# senpai.net
KiCad netlist of a schematic drawn in EAGLE
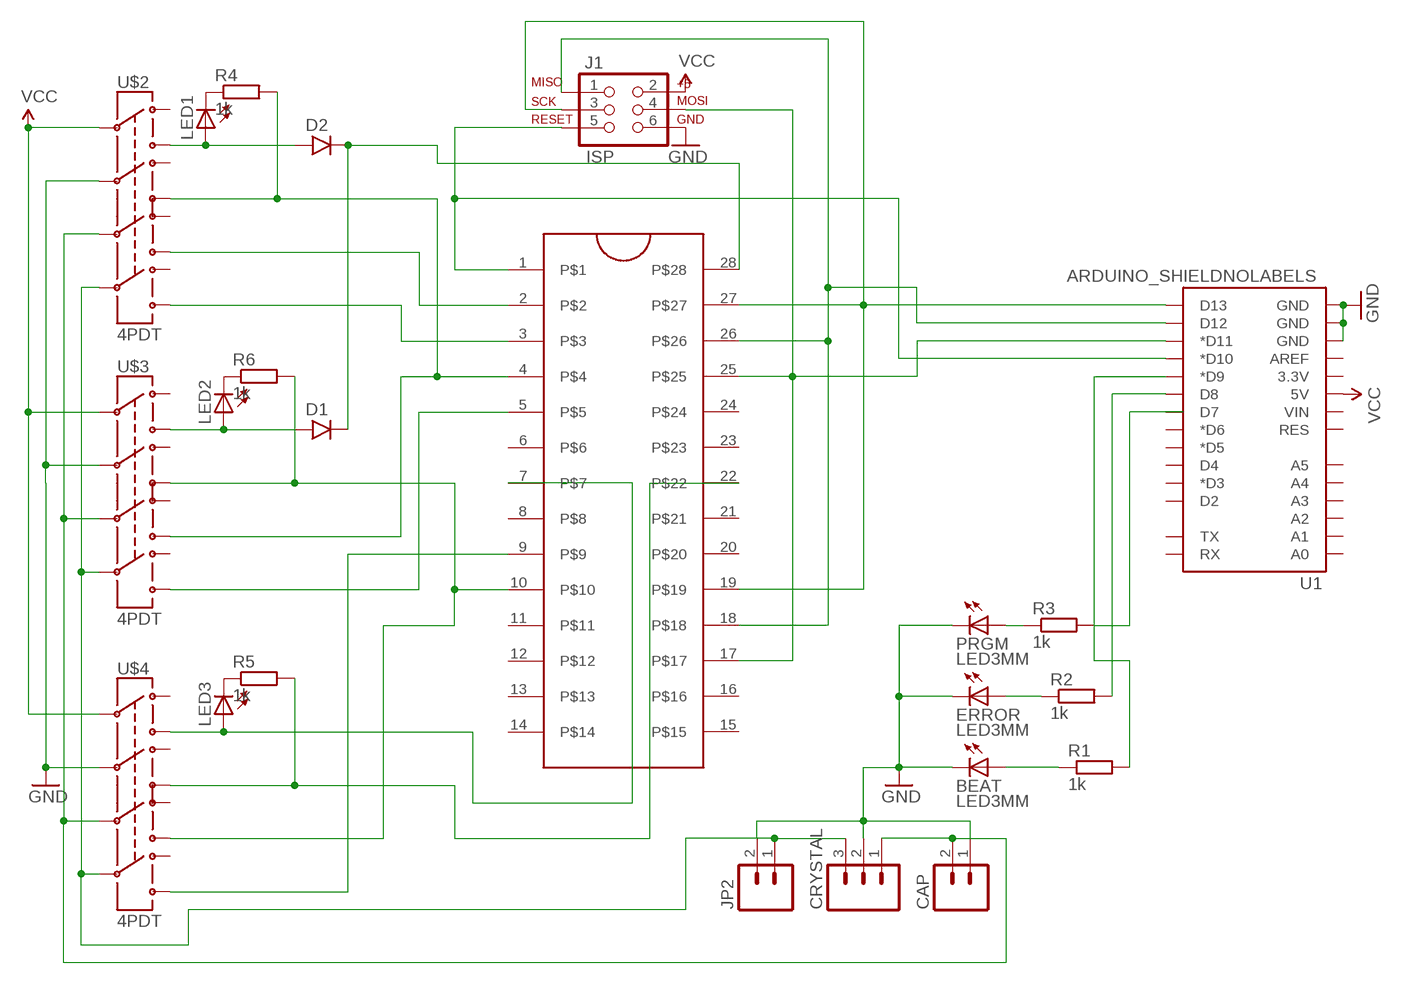
[diagram p0: schematic, sheet 1]

(export (version "E")
  (design (tool "Eeschema 10.0.6"))
  (components
    (comp (ref "BEAT")
      (value "LED3MM")
      (footprint "eagle-import:LED5MM")
      (libsource (lib "eagle-import") (part "LED5MM"))
    )
    (comp (ref "CAP")
      (value "M02PTH")
      (footprint "eagle-import:1X02")
      (libsource (lib "eagle-import") (part "M02PTH"))
    )
    (comp (ref "CRYSTAL")
      (value "M03LOCK")
      (footprint "eagle-import:1X03_LOCK")
      (libsource (lib "eagle-import") (part "M03LOCK"))
    )
    (comp (ref "D1")
      (value "DO41.2")
      (footprint "eagle-import:DO41-2")
      (libsource (lib "eagle-import") (part "DO41.2"))
    )
    (comp (ref "D2")
      (value "DO41.2")
      (footprint "eagle-import:DO41-2")
      (libsource (lib "eagle-import") (part "DO41.2"))
    )
    (comp (ref "ERROR")
      (value "LED3MM")
      (footprint "eagle-import:LED5MM")
      (libsource (lib "eagle-import") (part "LED5MM"))
    )
    (comp (ref "J1")
      (value "ISP")
      (footprint "eagle-import:2X3")
      (libsource (lib "eagle-import") (part "AVR_SPI_PRG_6PTH"))
    )
    (comp (ref "JP2")
      (value "M02PTH")
      (footprint "eagle-import:1X02")
      (libsource (lib "eagle-import") (part "M02PTH"))
    )
    (comp (ref "LED1")
      (value "LED5MM")
      (footprint "eagle-import:LED5MM")
      (libsource (lib "eagle-import") (part "LED5MM"))
    )
    (comp (ref "LED2")
      (value "LED5MM")
      (footprint "eagle-import:LED5MM")
      (libsource (lib "eagle-import") (part "LED5MM"))
    )
    (comp (ref "LED3")
      (value "LED5MM")
      (footprint "eagle-import:LED5MM")
      (libsource (lib "eagle-import") (part "LED5MM"))
    )
    (comp (ref "PRGM")
      (value "LED3MM")
      (footprint "eagle-import:LED5MM")
      (libsource (lib "eagle-import") (part "LED5MM"))
    )
    (comp (ref "R1")
      (value "1k")
      (footprint "eagle-import:0204_7")
      (libsource (lib "eagle-import") (part "R-EU_0204/7"))
    )
    (comp (ref "R2")
      (value "1k")
      (footprint "eagle-import:0204_7")
      (libsource (lib "eagle-import") (part "R-EU_0204/7"))
    )
    (comp (ref "R3")
      (value "1k")
      (footprint "eagle-import:0204_7")
      (libsource (lib "eagle-import") (part "R-EU_0204/7"))
    )
    (comp (ref "R4")
      (value "1k")
      (footprint "eagle-import:0204_7")
      (libsource (lib "eagle-import") (part "R-EU_0204/7"))
    )
    (comp (ref "R5")
      (value "1k")
      (footprint "eagle-import:0204_7")
      (libsource (lib "eagle-import") (part "R-EU_0204/7"))
    )
    (comp (ref "R6")
      (value "1k")
      (footprint "eagle-import:0204_7")
      (libsource (lib "eagle-import") (part "R-EU_0204/7"))
    )
    (comp (ref "U$1")
      (value "ZIFSOCKET-28-3ZIFFSOCKET-28-3")
      (footprint "eagle-import:DIL28-3-ZIF_SOCKET")
      (libsource (lib "eagle-import") (part "ZIFSOCKET-28-3ZIFFSOCKET-28-3"))
    )
    (comp (ref "U$2")
      (value "4PDT")
      (footprint "eagle-import:4PDT")
      (libsource (lib "eagle-import") (part "4PDT"))
    )
    (comp (ref "U$3")
      (value "4PDT")
      (footprint "eagle-import:4PDT")
      (libsource (lib "eagle-import") (part "4PDT"))
    )
    (comp (ref "U$4")
      (value "4PDT")
      (footprint "eagle-import:4PDT")
      (libsource (lib "eagle-import") (part "4PDT"))
    )
    (comp (ref "U1")
      (value "ARDUINO_SHIELDNOLABELS")
      (footprint "eagle-import:DUEMILANOVE_SHIELD_NOLABELS")
      (libsource (lib "eagle-import") (part "ARDUINO_SHIELDNOLABELS"))
    )
  )
  (nets
    (net (code "1") (name "GND") (class "Default")
      (node (ref "BEAT") (pin "K") (pinfunction "C_K") (pintype "passive"))
      (node (ref "CAP") (pin "1") (pinfunction "1_1") (pintype "passive"))
      (node (ref "CRYSTAL") (pin "2") (pinfunction "2_2") (pintype "passive"))
      (node (ref "ERROR") (pin "K") (pinfunction "C_K") (pintype "passive"))
      (node (ref "J1") (pin "6") (pinfunction "6_6") (pintype "passive"))
      (node (ref "JP2") (pin "2") (pinfunction "2_2") (pintype "passive"))
      (node (ref "PRGM") (pin "K") (pinfunction "C_K") (pintype "passive"))
      (node (ref "U$2") (pin "5") (pinfunction "5_5") (pintype "bidirectional"))
      (node (ref "U$3") (pin "5") (pinfunction "5_5") (pintype "bidirectional"))
      (node (ref "U$4") (pin "5") (pinfunction "5_5") (pintype "bidirectional"))
      (node (ref "U1") (pin "GND@0") (pinfunction "GND_GND@0") (pintype "bidirectional"))
      (node (ref "U1") (pin "GND@1") (pinfunction "GND_GND@1") (pintype "bidirectional"))
      (node (ref "U1") (pin "GND@2") (pinfunction "GND_GND@2") (pintype "bidirectional"))
    )
    (net (code "2") (name "Net-(BEAT-PadA)") (class "Default")
      (node (ref "BEAT") (pin "A") (pinfunction "A_A") (pintype "passive"))
      (node (ref "R1") (pin "1") (pinfunction "1_1") (pintype "passive"))
    )
    (net (code "3") (name "Net-(CAP-Pad2)") (class "Default")
      (node (ref "CAP") (pin "2") (pinfunction "2_2") (pintype "passive"))
      (node (ref "CRYSTAL") (pin "1") (pinfunction "1_1") (pintype "passive"))
      (node (ref "U$2") (pin "8") (pinfunction "8_8") (pintype "bidirectional"))
      (node (ref "U$3") (pin "8") (pinfunction "8_8") (pintype "bidirectional"))
      (node (ref "U$4") (pin "8") (pinfunction "8_8") (pintype "bidirectional"))
    )
    (net (code "4") (name "Net-(CRYSTAL-Pad3)") (class "Default")
      (node (ref "CRYSTAL") (pin "3") (pinfunction "3_3") (pintype "passive"))
      (node (ref "JP2") (pin "1") (pinfunction "1_1") (pintype "passive"))
      (node (ref "U$2") (pin "11") (pinfunction "11_11") (pintype "bidirectional"))
      (node (ref "U$3") (pin "11") (pinfunction "11_11") (pintype "bidirectional"))
      (node (ref "U$4") (pin "11") (pinfunction "11_11") (pintype "bidirectional"))
    )
    (net (code "5") (name "Net-(D1-PadA)") (class "Default")
      (node (ref "D1") (pin "A") (pinfunction "A_A") (pintype "passive"))
      (node (ref "LED2") (pin "A") (pinfunction "A_A") (pintype "passive"))
      (node (ref "U$3") (pin "3") (pinfunction "3_3") (pintype "bidirectional"))
    )
    (net (code "6") (name "Net-(D2-PadA)") (class "Default")
      (node (ref "D2") (pin "A") (pinfunction "A_A") (pintype "passive"))
      (node (ref "LED1") (pin "A") (pinfunction "A_A") (pintype "passive"))
      (node (ref "U$2") (pin "3") (pinfunction "3_3") (pintype "bidirectional"))
    )
    (net (code "7") (name "Net-(ERROR-PadA)") (class "Default")
      (node (ref "ERROR") (pin "A") (pinfunction "A_A") (pintype "passive"))
      (node (ref "R2") (pin "1") (pinfunction "1_1") (pintype "passive"))
    )
    (net (code "8") (name "Net-(LED1-C)") (class "Default")
      (node (ref "LED1") (pin "K") (pinfunction "C_K") (pintype "passive"))
      (node (ref "R4") (pin "1") (pinfunction "1_1") (pintype "passive"))
    )
    (net (code "9") (name "Net-(LED2-C)") (class "Default")
      (node (ref "LED2") (pin "K") (pinfunction "C_K") (pintype "passive"))
      (node (ref "R6") (pin "1") (pinfunction "1_1") (pintype "passive"))
    )
    (net (code "10") (name "Net-(LED3-C)") (class "Default")
      (node (ref "LED3") (pin "K") (pinfunction "C_K") (pintype "passive"))
      (node (ref "R5") (pin "1") (pinfunction "1_1") (pintype "passive"))
    )
    (net (code "11") (name "Net-(PRGM-PadA)") (class "Default")
      (node (ref "PRGM") (pin "A") (pinfunction "A_A") (pintype "passive"))
      (node (ref "R3") (pin "1") (pinfunction "1_1") (pintype "passive"))
    )
    (net (code "12") (name "Net-(R2-Pad2)") (class "Default")
      (node (ref "R2") (pin "2") (pinfunction "2_2") (pintype "passive"))
      (node (ref "U1") (pin "D8") (pinfunction "D8_D8") (pintype "bidirectional"))
    )
    (net (code "13") (name "Net-(R3-Pad2)") (class "Default")
      (node (ref "R3") (pin "2") (pinfunction "2_2") (pintype "passive"))
      (node (ref "U1") (pin "D7") (pinfunction "D7_D7") (pintype "bidirectional"))
    )
    (net (code "14") (name "Net-(U$1-P$1)") (class "Default")
      (node (ref "J1") (pin "5") (pinfunction "5_5") (pintype "passive"))
      (node (ref "U$1") (pin "1") (pinfunction "P$1_1") (pintype "bidirectional"))
      (node (ref "U1") (pin "D10") (pinfunction "*D10_D10") (pintype "bidirectional"))
    )
    (net (code "15") (name "Net-(U$1-P$2)") (class "Default")
      (node (ref "U$1") (pin "2") (pinfunction "P$2_2") (pintype "bidirectional"))
      (node (ref "U$2") (pin "9") (pinfunction "9_9") (pintype "bidirectional"))
    )
    (net (code "16") (name "Net-(U$1-P$3)") (class "Default")
      (node (ref "U$1") (pin "3") (pinfunction "P$3_3") (pintype "bidirectional"))
      (node (ref "U$2") (pin "12") (pinfunction "12_12") (pintype "bidirectional"))
    )
    (net (code "17") (name "Net-(U$1-P$4)") (class "Default")
      (node (ref "R4") (pin "2") (pinfunction "2_2") (pintype "passive"))
      (node (ref "U$1") (pin "4") (pinfunction "P$4_4") (pintype "bidirectional"))
      (node (ref "U$2") (pin "6") (pinfunction "6_6") (pintype "bidirectional"))
      (node (ref "U$3") (pin "9") (pinfunction "9_9") (pintype "bidirectional"))
    )
    (net (code "18") (name "Net-(U$1-P$5)") (class "Default")
      (node (ref "U$1") (pin "5") (pinfunction "P$5_5") (pintype "bidirectional"))
      (node (ref "U$3") (pin "12") (pinfunction "12_12") (pintype "bidirectional"))
    )
    (net (code "19") (name "Net-(U$1-P$7)") (class "Default")
      (node (ref "LED3") (pin "A") (pinfunction "A_A") (pintype "passive"))
      (node (ref "U$1") (pin "7") (pinfunction "P$7_7") (pintype "bidirectional"))
      (node (ref "U$4") (pin "3") (pinfunction "3_3") (pintype "bidirectional"))
    )
    (net (code "20") (name "Net-(U$1-P$9)") (class "Default")
      (node (ref "U$1") (pin "9") (pinfunction "P$9_9") (pintype "bidirectional"))
      (node (ref "U$4") (pin "12") (pinfunction "12_12") (pintype "bidirectional"))
    )
    (net (code "21") (name "Net-(U$1-P$10)") (class "Default")
      (node (ref "R6") (pin "2") (pinfunction "2_2") (pintype "passive"))
      (node (ref "U$1") (pin "10") (pinfunction "P$10_10") (pintype "bidirectional"))
      (node (ref "U$3") (pin "6") (pinfunction "6_6") (pintype "bidirectional"))
      (node (ref "U$4") (pin "9") (pinfunction "9_9") (pintype "bidirectional"))
    )
    (net (code "22") (name "Net-(U$1-P$17)") (class "Default")
      (node (ref "J1") (pin "4") (pinfunction "4_4") (pintype "passive"))
      (node (ref "U$1") (pin "17") (pinfunction "P$17_17") (pintype "bidirectional"))
      (node (ref "U$1") (pin "25") (pinfunction "P$25_25") (pintype "bidirectional"))
      (node (ref "U1") (pin "D11") (pinfunction "*D11_D11") (pintype "bidirectional"))
    )
    (net (code "23") (name "Net-(U$1-P$18)") (class "Default")
      (node (ref "J1") (pin "1") (pinfunction "1_1") (pintype "passive"))
      (node (ref "U$1") (pin "18") (pinfunction "P$18_18") (pintype "bidirectional"))
      (node (ref "U$1") (pin "26") (pinfunction "P$26_26") (pintype "bidirectional"))
      (node (ref "U1") (pin "D12") (pinfunction "D12_D12") (pintype "bidirectional"))
    )
    (net (code "24") (name "Net-(U$1-P$19)") (class "Default")
      (node (ref "J1") (pin "3") (pinfunction "3_3") (pintype "passive"))
      (node (ref "U$1") (pin "19") (pinfunction "P$19_19") (pintype "bidirectional"))
      (node (ref "U$1") (pin "27") (pinfunction "P$27_27") (pintype "bidirectional"))
      (node (ref "U1") (pin "D13") (pinfunction "D13_D13") (pintype "bidirectional"))
    )
    (net (code "25") (name "Net-(U$1-P$22)") (class "Default")
      (node (ref "R5") (pin "2") (pinfunction "2_2") (pintype "passive"))
      (node (ref "U$1") (pin "22") (pinfunction "P$22_22") (pintype "bidirectional"))
      (node (ref "U$4") (pin "6") (pinfunction "6_6") (pintype "bidirectional"))
    )
    (net (code "26") (name "Net-(U$1-P$28)") (class "Default")
      (node (ref "D1") (pin "C") (pinfunction "C_C") (pintype "passive"))
      (node (ref "D2") (pin "C") (pinfunction "C_C") (pintype "passive"))
      (node (ref "U$1") (pin "28") (pinfunction "P$28_28") (pintype "bidirectional"))
    )
    (net (code "27") (name "Net-(U1-*D9)") (class "Default")
      (node (ref "R1") (pin "2") (pinfunction "2_2") (pintype "passive"))
      (node (ref "U1") (pin "D9") (pinfunction "*D9_D9") (pintype "bidirectional"))
    )
    (net (code "28") (name "VCC") (class "Default")
      (node (ref "J1") (pin "2") (pinfunction "2_2") (pintype "passive"))
      (node (ref "U$2") (pin "2") (pinfunction "2_2") (pintype "bidirectional"))
      (node (ref "U$3") (pin "2") (pinfunction "2_2") (pintype "bidirectional"))
      (node (ref "U$4") (pin "2") (pinfunction "2_2") (pintype "bidirectional"))
      (node (ref "U1") (pin "5V") (pinfunction "5V_5V") (pintype "bidirectional"))
    )
    (net (code "29") (name "unconnected-(U$1-P$6-Pad6)") (class "Default")
      (node (ref "U$1") (pin "6") (pinfunction "P$6_6") (pintype "bidirectional"))
    )
    (net (code "30") (name "unconnected-(U$1-P$8-Pad8)") (class "Default")
      (node (ref "U$1") (pin "8") (pinfunction "P$8_8") (pintype "bidirectional"))
    )
    (net (code "31") (name "unconnected-(U$1-P$11-Pad11)") (class "Default")
      (node (ref "U$1") (pin "11") (pinfunction "P$11_11") (pintype "bidirectional"))
    )
    (net (code "32") (name "unconnected-(U$1-P$12-Pad12)") (class "Default")
      (node (ref "U$1") (pin "12") (pinfunction "P$12_12") (pintype "bidirectional"))
    )
    (net (code "33") (name "unconnected-(U$1-P$13-Pad13)") (class "Default")
      (node (ref "U$1") (pin "13") (pinfunction "P$13_13") (pintype "bidirectional"))
    )
    (net (code "34") (name "unconnected-(U$1-P$14-Pad14)") (class "Default")
      (node (ref "U$1") (pin "14") (pinfunction "P$14_14") (pintype "bidirectional"))
    )
    (net (code "35") (name "unconnected-(U$1-P$15-Pad15)") (class "Default")
      (node (ref "U$1") (pin "15") (pinfunction "P$15_15") (pintype "bidirectional"))
    )
    (net (code "36") (name "unconnected-(U$1-P$16-Pad16)") (class "Default")
      (node (ref "U$1") (pin "16") (pinfunction "P$16_16") (pintype "bidirectional"))
    )
    (net (code "37") (name "unconnected-(U$1-P$20-Pad20)") (class "Default")
      (node (ref "U$1") (pin "20") (pinfunction "P$20_20") (pintype "bidirectional"))
    )
    (net (code "38") (name "unconnected-(U$1-P$21-Pad21)") (class "Default")
      (node (ref "U$1") (pin "21") (pinfunction "P$21_21") (pintype "bidirectional"))
    )
    (net (code "39") (name "unconnected-(U$1-P$23-Pad23)") (class "Default")
      (node (ref "U$1") (pin "23") (pinfunction "P$23_23") (pintype "bidirectional"))
    )
    (net (code "40") (name "unconnected-(U$1-P$24-Pad24)") (class "Default")
      (node (ref "U$1") (pin "24") (pinfunction "P$24_24") (pintype "bidirectional"))
    )
    (net (code "41") (name "unconnected-(U$2-Pad1)") (class "Default")
      (node (ref "U$2") (pin "1") (pinfunction "1_1") (pintype "bidirectional"))
    )
    (net (code "42") (name "unconnected-(U$2-Pad4)") (class "Default")
      (node (ref "U$2") (pin "4") (pinfunction "4_4") (pintype "bidirectional"))
    )
    (net (code "43") (name "unconnected-(U$2-Pad7)") (class "Default")
      (node (ref "U$2") (pin "7") (pinfunction "7_7") (pintype "bidirectional"))
    )
    (net (code "44") (name "unconnected-(U$2-Pad10)") (class "Default")
      (node (ref "U$2") (pin "10") (pinfunction "10_10") (pintype "bidirectional"))
    )
    (net (code "45") (name "unconnected-(U$3-Pad1)") (class "Default")
      (node (ref "U$3") (pin "1") (pinfunction "1_1") (pintype "bidirectional"))
    )
    (net (code "46") (name "unconnected-(U$3-Pad4)") (class "Default")
      (node (ref "U$3") (pin "4") (pinfunction "4_4") (pintype "bidirectional"))
    )
    (net (code "47") (name "unconnected-(U$3-Pad7)") (class "Default")
      (node (ref "U$3") (pin "7") (pinfunction "7_7") (pintype "bidirectional"))
    )
    (net (code "48") (name "unconnected-(U$3-Pad10)") (class "Default")
      (node (ref "U$3") (pin "10") (pinfunction "10_10") (pintype "bidirectional"))
    )
    (net (code "49") (name "unconnected-(U$4-Pad1)") (class "Default")
      (node (ref "U$4") (pin "1") (pinfunction "1_1") (pintype "bidirectional"))
    )
    (net (code "50") (name "unconnected-(U$4-Pad4)") (class "Default")
      (node (ref "U$4") (pin "4") (pinfunction "4_4") (pintype "bidirectional"))
    )
    (net (code "51") (name "unconnected-(U$4-Pad7)") (class "Default")
      (node (ref "U$4") (pin "7") (pinfunction "7_7") (pintype "bidirectional"))
    )
    (net (code "52") (name "unconnected-(U$4-Pad10)") (class "Default")
      (node (ref "U$4") (pin "10") (pinfunction "10_10") (pintype "bidirectional"))
    )
    (net (code "53") (name "unconnected-(U1-*D3-PadD3)") (class "Default")
      (node (ref "U1") (pin "D3") (pinfunction "*D3_D3") (pintype "bidirectional"))
    )
    (net (code "54") (name "unconnected-(U1-*D5-PadD5)") (class "Default")
      (node (ref "U1") (pin "D5") (pinfunction "*D5_D5") (pintype "bidirectional"))
    )
    (net (code "55") (name "unconnected-(U1-*D6-PadD6)") (class "Default")
      (node (ref "U1") (pin "D6") (pinfunction "*D6_D6") (pintype "bidirectional"))
    )
    (net (code "56") (name "unconnected-(U1-Pad3.3V)") (class "Default")
      (node (ref "U1") (pin "3.3V") (pinfunction "3.3V_3.3V") (pintype "bidirectional"))
    )
    (net (code "57") (name "unconnected-(U1-PadA0)") (class "Default")
      (node (ref "U1") (pin "A0") (pinfunction "A0_A0") (pintype "bidirectional"))
    )
    (net (code "58") (name "unconnected-(U1-PadA1)") (class "Default")
      (node (ref "U1") (pin "A1") (pinfunction "A1_A1") (pintype "bidirectional"))
    )
    (net (code "59") (name "unconnected-(U1-PadA2)") (class "Default")
      (node (ref "U1") (pin "A2") (pinfunction "A2_A2") (pintype "bidirectional"))
    )
    (net (code "60") (name "unconnected-(U1-PadA3)") (class "Default")
      (node (ref "U1") (pin "A3") (pinfunction "A3_A3") (pintype "bidirectional"))
    )
    (net (code "61") (name "unconnected-(U1-PadA4)") (class "Default")
      (node (ref "U1") (pin "A4") (pinfunction "A4_A4") (pintype "bidirectional"))
    )
    (net (code "62") (name "unconnected-(U1-PadA5)") (class "Default")
      (node (ref "U1") (pin "A5") (pinfunction "A5_A5") (pintype "bidirectional"))
    )
    (net (code "63") (name "unconnected-(U1-PadAREF)") (class "Default")
      (node (ref "U1") (pin "AREF") (pinfunction "AREF_AREF") (pintype "bidirectional"))
    )
    (net (code "64") (name "unconnected-(U1-PadD2)") (class "Default")
      (node (ref "U1") (pin "D2") (pinfunction "D2_D2") (pintype "bidirectional"))
    )
    (net (code "65") (name "unconnected-(U1-PadD4)") (class "Default")
      (node (ref "U1") (pin "D4") (pinfunction "D4_D4") (pintype "bidirectional"))
    )
    (net (code "66") (name "unconnected-(U1-PadRES)") (class "Default")
      (node (ref "U1") (pin "RES") (pinfunction "RES_RES") (pintype "bidirectional"))
    )
    (net (code "67") (name "unconnected-(U1-PadRX)") (class "Default")
      (node (ref "U1") (pin "RX") (pinfunction "RX_RX") (pintype "bidirectional"))
    )
    (net (code "68") (name "unconnected-(U1-PadTX)") (class "Default")
      (node (ref "U1") (pin "TX") (pinfunction "TX_TX") (pintype "bidirectional"))
    )
    (net (code "69") (name "unconnected-(U1-PadVIN)") (class "Default")
      (node (ref "U1") (pin "VIN") (pinfunction "VIN_VIN") (pintype "bidirectional"))
    )
  )
)
